# simple.net
KiCad netlist of a schematic drawn in EAGLE
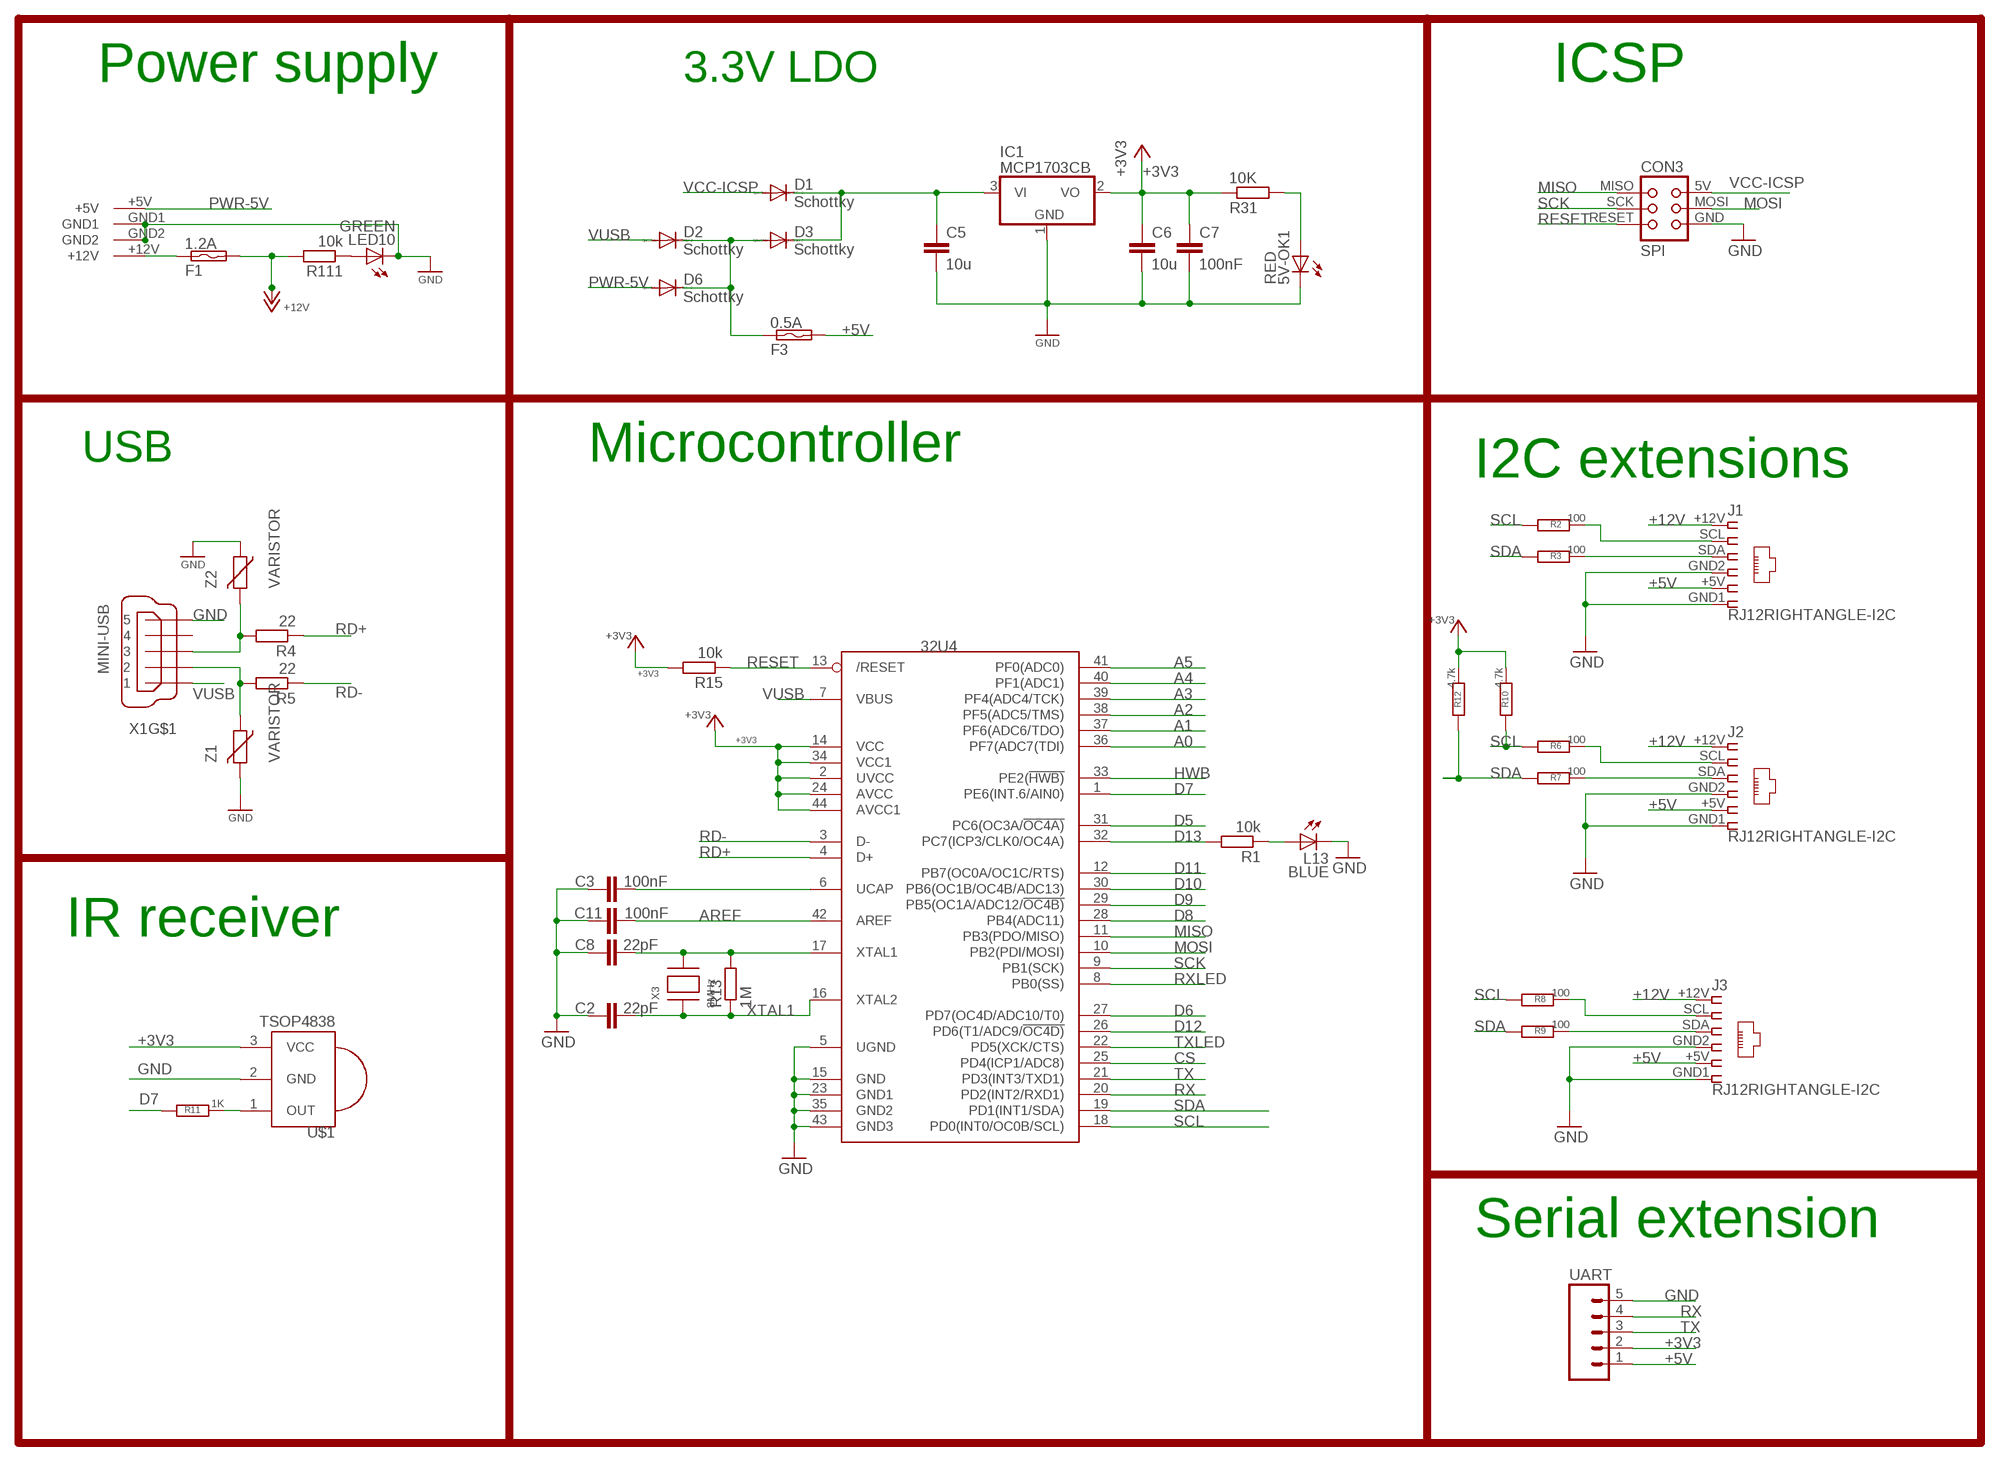
[diagram p0: schematic, sheet 1]

(export (version "E")
  (design (tool "Eeschema 10.0.6"))
  (components
    (comp (ref "5V-OK1")
      (value "RED")
      (footprint "eagle-import:CHIP-LED0805")
      (libsource (lib "eagle-import") (part "LEDCHIP-LED0805"))
    )
    (comp (ref "C2")
      (value "22pF")
      (footprint "eagle-import:C0805K")
      (libsource (lib "eagle-import") (part "C-EUC0805K"))
    )
    (comp (ref "C3")
      (value "100nF")
      (footprint "eagle-import:C0805K")
      (libsource (lib "eagle-import") (part "C-EUC0805K"))
    )
    (comp (ref "C5")
      (value "10u")
      (footprint "eagle-import:C0805K")
      (fields (field (name "MPN") "77-VJ1206V106ZXQTBC"))
      (libsource (lib "eagle-import") (part "rcl_334_C-EUC0805K"))
    )
    (comp (ref "C6")
      (value "10u")
      (footprint "eagle-import:C0805K")
      (fields (field (name "MPN") "77-VJ1206V106ZXQTBC"))
      (libsource (lib "eagle-import") (part "rcl_334_C-EUC0805K"))
    )
    (comp (ref "C7")
      (value "100nF")
      (footprint "eagle-import:C0805K")
      (fields (field (name "MPN") "80-C1206C104K5R"))
      (libsource (lib "eagle-import") (part "rcl_334_C-EUC0805K"))
    )
    (comp (ref "C8")
      (value "22pF")
      (footprint "eagle-import:C0805K")
      (libsource (lib "eagle-import") (part "C-EUC0805K"))
    )
    (comp (ref "C11")
      (value "100nF")
      (footprint "eagle-import:C0805K")
      (libsource (lib "eagle-import") (part "C-EUC0805K"))
    )
    (comp (ref "CON3")
      (value "SPI")
      (footprint "eagle-import:TC2030-MCP-NL")
      (libsource (lib "eagle-import") (part "TINYISPT"))
    )
    (comp (ref "D1")
      (value "Schottky")
      (footprint "eagle-import:SOD123")
      (fields (field (name "MPN") "621-1N5819HW-F"))
      (libsource (lib "eagle-import") (part "MBR0520LT"))
    )
    (comp (ref "D2")
      (value "Schottky")
      (footprint "eagle-import:SOD123")
      (fields (field (name "MPN") "621-1N5819HW-F"))
      (libsource (lib "eagle-import") (part "MBR0520LT"))
    )
    (comp (ref "D3")
      (value "Schottky")
      (footprint "eagle-import:SOD123")
      (fields (field (name "MPN") "621-1N5819HW-F"))
      (libsource (lib "eagle-import") (part "MBR0520LT"))
    )
    (comp (ref "D6")
      (value "Schottky")
      (footprint "eagle-import:SOD123")
      (fields (field (name "MPN") "621-1N5819HW-F"))
      (libsource (lib "eagle-import") (part "MBR0520LT"))
    )
    (comp (ref "F1")
      (value "1.2A")
      (footprint "eagle-import:C1812")
      (libsource (lib "eagle-import") (part "POLYSWITCHSMD1812"))
    )
    (comp (ref "F3")
      (value "0.5A")
      (footprint "eagle-import:C1812")
      (libsource (lib "eagle-import") (part "POLYSWITCHSMD1812"))
    )
    (comp (ref "IC1")
      (value "MCP1703CB")
      (footprint "eagle-import:SOT23")
      (libsource (lib "eagle-import") (part "MCP1703CB"))
    )
    (comp (ref "J1")
      (value "RJ12RIGHTANGLE-I2C")
      (footprint "eagle-import:RJ12-RIGHTANGLE-I2C")
      (libsource (lib "eagle-import") (part "RJ12RIGHTANGLE-I2C"))
    )
    (comp (ref "J2")
      (value "RJ12RIGHTANGLE-I2C")
      (footprint "eagle-import:RJ12-RIGHTANGLE-I2C")
      (libsource (lib "eagle-import") (part "RJ12RIGHTANGLE-I2C"))
    )
    (comp (ref "J3")
      (value "RJ12RIGHTANGLE-I2C")
      (footprint "eagle-import:RJ12-RIGHTANGLE-I2C")
      (libsource (lib "eagle-import") (part "RJ12RIGHTANGLE-I2C"))
    )
    (comp (ref "L13")
      (value "BLUE")
      (footprint "eagle-import:CHIP-LED0805")
      (libsource (lib "eagle-import") (part "LEDCHIP-LED0805"))
    )
    (comp (ref "LED10")
      (value "GREEN")
      (footprint "eagle-import:CHIP-LED0805")
      (libsource (lib "eagle-import") (part "LEDCHIP-LED0805"))
    )
    (comp (ref "R1")
      (value "10k")
      (footprint "eagle-import:M0805")
      (libsource (lib "eagle-import") (part "resistor_348_R-EU_M0805"))
    )
    (comp (ref "R2")
      (value "100")
      (footprint "eagle-import:R0805")
      (libsource (lib "eagle-import") (part "resistor_348_R-EU_R0805"))
    )
    (comp (ref "R3")
      (value "100")
      (footprint "eagle-import:R0805")
      (libsource (lib "eagle-import") (part "resistor_348_R-EU_R0805"))
    )
    (comp (ref "R4")
      (value "22")
      (footprint "eagle-import:R0805")
      (libsource (lib "eagle-import") (part "R-EU_R0805"))
    )
    (comp (ref "R5")
      (value "22")
      (footprint "eagle-import:R0805")
      (libsource (lib "eagle-import") (part "rcl_334_R-EU_R0805"))
    )
    (comp (ref "R6")
      (value "100")
      (footprint "eagle-import:R0805")
      (libsource (lib "eagle-import") (part "resistor_348_R-EU_R0805"))
    )
    (comp (ref "R7")
      (value "100")
      (footprint "eagle-import:R0805")
      (libsource (lib "eagle-import") (part "resistor_348_R-EU_R0805"))
    )
    (comp (ref "R8")
      (value "100")
      (footprint "eagle-import:R0805")
      (libsource (lib "eagle-import") (part "resistor_348_R-EU_R0805"))
    )
    (comp (ref "R9")
      (value "100")
      (footprint "eagle-import:R0805")
      (libsource (lib "eagle-import") (part "resistor_348_R-EU_R0805"))
    )
    (comp (ref "R10")
      (value "4.7k")
      (footprint "eagle-import:R0805")
      (libsource (lib "eagle-import") (part "resistor_348_R-EU_R0805"))
    )
    (comp (ref "R11")
      (value "1K")
      (footprint "eagle-import:R0805")
      (libsource (lib "eagle-import") (part "resistor_348_R-EU_R0805"))
    )
    (comp (ref "R12")
      (value "4.7k")
      (footprint "eagle-import:R0805")
      (libsource (lib "eagle-import") (part "resistor_348_R-EU_R0805"))
    )
    (comp (ref "R13")
      (value "1M")
      (footprint "eagle-import:M0805")
      (libsource (lib "eagle-import") (part "R-EU_M0805"))
    )
    (comp (ref "R15")
      (value "10k")
      (footprint "eagle-import:M0805")
      (libsource (lib "eagle-import") (part "resistor_348_R-EU_M0805"))
    )
    (comp (ref "R31")
      (value "10K")
      (footprint "eagle-import:R0805")
      (libsource (lib "eagle-import") (part "resistor_348_R-EU_R0805"))
    )
    (comp (ref "R111")
      (value "10k")
      (footprint "eagle-import:R0805")
      (libsource (lib "eagle-import") (part "R-EU_R0805"))
    )
    (comp (ref "U$1")
      (value "TSOP4838")
      (footprint "eagle-import:PNA460XM")
      (libsource (lib "eagle-import") (part "PNA460XM"))
    )
    (comp (ref "U$4")
      (value "32U4")
      (footprint "eagle-import:TQFP44")
      (libsource (lib "eagle-import") (part "ATMEGA32U4-AU"))
    )
    (comp (ref "U$6")
      (value "KPJX-4S-S")
      (footprint "eagle-import:KPJX-4S-S")
      (libsource (lib "eagle-import") (part "KPJX-4S-S"))
    )
    (comp (ref "UART")
      (value "M05PTH")
      (footprint "eagle-import:1X05")
      (libsource (lib "eagle-import") (part "M05PTH"))
    )
    (comp (ref "X1")
      (value "MINI-USB")
      (footprint "eagle-import:32005-201")
      (fields (field (name "MPN") "649-10033526-N3212LF"))
      (libsource (lib "eagle-import") (part "MINI-USB-SCHIELD-32005-201"))
    )
    (comp (ref "X3")
      (value "8MHz")
      (footprint "eagle-import:NX6035")
      (libsource (lib "eagle-import") (part "XTALNX6035"))
    )
    (comp (ref "Z1")
      (value "VARISTOR")
      (footprint "eagle-import:CT_CN0603")
      (libsource (lib "eagle-import") (part "VARISTORCN0603"))
    )
    (comp (ref "Z2")
      (value "VARISTOR")
      (footprint "eagle-import:CT_CN0603")
      (libsource (lib "eagle-import") (part "VARISTORCN0603"))
    )
  )
  (nets
    (net (code "1") (name "+3V3") (class "Default")
      (node (ref "C6") (pin "1") (pinfunction "1_1") (pintype "passive"))
      (node (ref "C7") (pin "1") (pinfunction "1_1") (pintype "passive"))
      (node (ref "IC1") (pin "2") (pinfunction "VO_2") (pintype "passive"))
      (node (ref "R10") (pin "1") (pinfunction "1_1") (pintype "passive"))
      (node (ref "R12") (pin "1") (pinfunction "1_1") (pintype "passive"))
      (node (ref "R15") (pin "2") (pinfunction "2_2") (pintype "passive"))
      (node (ref "R31") (pin "1") (pinfunction "1_1") (pintype "passive"))
      (node (ref "U$1") (pin "3") (pinfunction "VCC_3") (pintype "power_in"))
      (node (ref "U$4") (pin "14") (pinfunction "VCC_14") (pintype "bidirectional"))
      (node (ref "U$4") (pin "2") (pinfunction "UVCC_2") (pintype "bidirectional"))
      (node (ref "U$4") (pin "24") (pinfunction "AVCC_24") (pintype "bidirectional"))
      (node (ref "U$4") (pin "34") (pinfunction "VCC1_34") (pintype "bidirectional"))
      (node (ref "U$4") (pin "44") (pinfunction "AVCC1_44") (pintype "bidirectional"))
      (node (ref "UART") (pin "2") (pinfunction "2_2") (pintype "passive"))
    )
    (net (code "2") (name "+12V") (class "Default")
      (node (ref "F1") (pin "2") (pinfunction "2_2") (pintype "passive"))
      (node (ref "J1") (pin "+12V") (pinfunction "1_+12V") (pintype "bidirectional"))
      (node (ref "J2") (pin "+12V") (pinfunction "1_+12V") (pintype "bidirectional"))
      (node (ref "J3") (pin "+12V") (pinfunction "1_+12V") (pintype "bidirectional"))
      (node (ref "R111") (pin "2") (pinfunction "2_2") (pintype "passive"))
    )
    (net (code "3") (name "/+5V") (class "Default")
      (node (ref "F3") (pin "2") (pinfunction "2_2") (pintype "passive"))
      (node (ref "J1") (pin "+5V") (pinfunction "5_+5V") (pintype "bidirectional"))
      (node (ref "J2") (pin "+5V") (pinfunction "5_+5V") (pintype "bidirectional"))
      (node (ref "J3") (pin "+5V") (pinfunction "5_+5V") (pintype "bidirectional"))
      (node (ref "UART") (pin "1") (pinfunction "1_1") (pintype "passive"))
    )
    (net (code "4") (name "/A0") (class "Default")
      (node (ref "U$4") (pin "36") (pinfunction "PF7(ADC7(TDI)_36") (pintype "bidirectional"))
    )
    (net (code "5") (name "/A1") (class "Default")
      (node (ref "U$4") (pin "37") (pinfunction "PF6(ADC6/TDO)_37") (pintype "bidirectional"))
    )
    (net (code "6") (name "/A2") (class "Default")
      (node (ref "U$4") (pin "38") (pinfunction "PF5(ADC5/TMS)_38") (pintype "bidirectional"))
    )
    (net (code "7") (name "/A3") (class "Default")
      (node (ref "U$4") (pin "39") (pinfunction "PF4(ADC4/TCK)_39") (pintype "bidirectional"))
    )
    (net (code "8") (name "/A4") (class "Default")
      (node (ref "U$4") (pin "40") (pinfunction "PF1(ADC1)_40") (pintype "bidirectional"))
    )
    (net (code "9") (name "/A5") (class "Default")
      (node (ref "U$4") (pin "41") (pinfunction "PF0(ADC0)_41") (pintype "bidirectional"))
    )
    (net (code "10") (name "/AREF") (class "Default")
      (node (ref "C11") (pin "1") (pinfunction "1_1") (pintype "passive"))
      (node (ref "U$4") (pin "42") (pinfunction "AREF_42") (pintype "bidirectional"))
    )
    (net (code "11") (name "/CS") (class "Default")
      (node (ref "U$4") (pin "25") (pinfunction "PD4(ICP1/ADC8)_25") (pintype "bidirectional"))
    )
    (net (code "12") (name "/D5") (class "Default")
      (node (ref "U$4") (pin "31") (pinfunction "PC6(OC3A/~{OC4A})_31") (pintype "bidirectional"))
    )
    (net (code "13") (name "/D6") (class "Default")
      (node (ref "U$4") (pin "27") (pinfunction "PD7(OC4D/ADC10/T0)_27") (pintype "bidirectional"))
    )
    (net (code "14") (name "/D7") (class "Default")
      (node (ref "R11") (pin "2") (pinfunction "2_2") (pintype "passive"))
      (node (ref "U$4") (pin "1") (pinfunction "PE6(INT.6/AIN0)_1") (pintype "bidirectional"))
    )
    (net (code "15") (name "/D8") (class "Default")
      (node (ref "U$4") (pin "28") (pinfunction "PB4(ADC11)_28") (pintype "bidirectional"))
    )
    (net (code "16") (name "/D9") (class "Default")
      (node (ref "U$4") (pin "29") (pinfunction "PB5(OC1A/ADC12/~{OC4B})_29") (pintype "bidirectional"))
    )
    (net (code "17") (name "/D10") (class "Default")
      (node (ref "U$4") (pin "30") (pinfunction "PB6(OC1B/OC4B/ADC13)_30") (pintype "bidirectional"))
    )
    (net (code "18") (name "/D11") (class "Default")
      (node (ref "U$4") (pin "12") (pinfunction "PB7(OC0A/OC1C/RTS)_12") (pintype "bidirectional"))
    )
    (net (code "19") (name "/D12") (class "Default")
      (node (ref "U$4") (pin "26") (pinfunction "PD6(T1/ADC9/~{OC4D})_26") (pintype "bidirectional"))
    )
    (net (code "20") (name "/D13") (class "Default")
      (node (ref "R1") (pin "2") (pinfunction "2_2") (pintype "passive"))
      (node (ref "U$4") (pin "32") (pinfunction "PC7(ICP3/CLK0/OC4A)_32") (pintype "bidirectional"))
    )
    (net (code "21") (name "/HWB") (class "Default")
      (node (ref "U$4") (pin "33") (pinfunction "PE2(~{HWB})_33") (pintype "bidirectional"))
    )
    (net (code "22") (name "/MISO") (class "Default")
      (node (ref "CON3") (pin "MISO") (pinfunction "MISO_MISO") (pintype "passive"))
      (node (ref "U$4") (pin "11") (pinfunction "PB3(PDO/MISO)_11") (pintype "bidirectional"))
    )
    (net (code "23") (name "/MOSI") (class "Default")
      (node (ref "CON3") (pin "MOSI") (pinfunction "MOSI_MOSI") (pintype "passive"))
      (node (ref "U$4") (pin "10") (pinfunction "PB2(PDI/MOSI)_10") (pintype "bidirectional"))
    )
    (net (code "24") (name "/PWR-5V") (class "Default")
      (node (ref "D6") (pin "A") (pinfunction "A_A") (pintype "passive"))
      (node (ref "U$6") (pin "+5V") (pinfunction "+5V_+5V") (pintype "power_in"))
    )
    (net (code "25") (name "/RD+") (class "Default")
      (node (ref "R4") (pin "1") (pinfunction "1_1") (pintype "passive"))
      (node (ref "U$4") (pin "4") (pinfunction "D+_4") (pintype "bidirectional"))
    )
    (net (code "26") (name "/RD-") (class "Default")
      (node (ref "R5") (pin "1") (pinfunction "1_1") (pintype "passive"))
      (node (ref "U$4") (pin "3") (pinfunction "D-_3") (pintype "bidirectional"))
    )
    (net (code "27") (name "/RESET") (class "Default")
      (node (ref "CON3") (pin "RESET") (pinfunction "RESET_RESET") (pintype "passive"))
      (node (ref "R15") (pin "1") (pinfunction "1_1") (pintype "passive"))
      (node (ref "U$4") (pin "13") (pinfunction "/RESET_13") (pintype "bidirectional"))
    )
    (net (code "28") (name "/RX") (class "Default")
      (node (ref "U$4") (pin "20") (pinfunction "PD2(INT2/RXD1)_20") (pintype "bidirectional"))
      (node (ref "UART") (pin "4") (pinfunction "4_4") (pintype "passive"))
    )
    (net (code "29") (name "/RXLED") (class "Default")
      (node (ref "U$4") (pin "8") (pinfunction "PB0(SS)_8") (pintype "bidirectional"))
    )
    (net (code "30") (name "/SCK") (class "Default")
      (node (ref "CON3") (pin "SCK") (pinfunction "SCK_SCK") (pintype "passive"))
      (node (ref "U$4") (pin "9") (pinfunction "PB1(SCK)_9") (pintype "bidirectional"))
    )
    (net (code "31") (name "/SCL") (class "Default")
      (node (ref "R10") (pin "2") (pinfunction "2_2") (pintype "passive"))
      (node (ref "R2") (pin "2") (pinfunction "2_2") (pintype "passive"))
      (node (ref "R6") (pin "2") (pinfunction "2_2") (pintype "passive"))
      (node (ref "R8") (pin "2") (pinfunction "2_2") (pintype "passive"))
      (node (ref "U$4") (pin "18") (pinfunction "PD0(INT0/OC0B/SCL)_18") (pintype "bidirectional"))
    )
    (net (code "32") (name "/SDA") (class "Default")
      (node (ref "R12") (pin "2") (pinfunction "2_2") (pintype "passive"))
      (node (ref "R3") (pin "2") (pinfunction "2_2") (pintype "passive"))
      (node (ref "R7") (pin "2") (pinfunction "2_2") (pintype "passive"))
      (node (ref "R9") (pin "2") (pinfunction "2_2") (pintype "passive"))
      (node (ref "U$4") (pin "19") (pinfunction "PD1(INT1/SDA)_19") (pintype "bidirectional"))
    )
    (net (code "33") (name "/TX") (class "Default")
      (node (ref "U$4") (pin "21") (pinfunction "PD3(INT3/TXD1)_21") (pintype "bidirectional"))
      (node (ref "UART") (pin "3") (pinfunction "3_3") (pintype "passive"))
    )
    (net (code "34") (name "/TXLED") (class "Default")
      (node (ref "U$4") (pin "22") (pinfunction "PD5(XCK/CTS)_22") (pintype "bidirectional"))
    )
    (net (code "35") (name "/VCC-ICSP") (class "Default")
      (node (ref "CON3") (pin "5V") (pinfunction "VCC_5V") (pintype "passive"))
      (node (ref "D1") (pin "A") (pinfunction "A_A") (pintype "passive"))
    )
    (net (code "36") (name "/VUSB") (class "Default")
      (node (ref "D2") (pin "A") (pinfunction "A_A") (pintype "passive"))
      (node (ref "U$4") (pin "7") (pinfunction "VBUS_7") (pintype "bidirectional"))
      (node (ref "X1") (pin "1") (pinfunction "1_1") (pintype "passive"))
    )
    (net (code "37") (name "/XTAL1") (class "Default")
      (node (ref "C2") (pin "2") (pinfunction "2_2") (pintype "passive"))
      (node (ref "R13") (pin "1") (pinfunction "1_1") (pintype "passive"))
      (node (ref "U$4") (pin "16") (pinfunction "XTAL2_16") (pintype "bidirectional"))
      (node (ref "X3") (pin "P$1") (pinfunction "P$1_P$1") (pintype "bidirectional"))
    )
    (net (code "38") (name "GND") (class "Default")
      (node (ref "5V-OK1") (pin "C") (pinfunction "C_C") (pintype "passive"))
      (node (ref "C11") (pin "2") (pinfunction "2_2") (pintype "passive"))
      (node (ref "C2") (pin "1") (pinfunction "1_1") (pintype "passive"))
      (node (ref "C3") (pin "1") (pinfunction "1_1") (pintype "passive"))
      (node (ref "C5") (pin "2") (pinfunction "2_2") (pintype "passive"))
      (node (ref "C6") (pin "2") (pinfunction "2_2") (pintype "passive"))
      (node (ref "C7") (pin "2") (pinfunction "2_2") (pintype "passive"))
      (node (ref "C8") (pin "1") (pinfunction "1_1") (pintype "passive"))
      (node (ref "CON3") (pin "GND") (pinfunction "GND_GND") (pintype "passive"))
      (node (ref "IC1") (pin "1") (pinfunction "GND_1") (pintype "passive"))
      (node (ref "J1") (pin "GND1") (pinfunction "6_GND1") (pintype "bidirectional"))
      (node (ref "J1") (pin "GND2") (pinfunction "4_GND2") (pintype "bidirectional"))
      (node (ref "J2") (pin "GND1") (pinfunction "6_GND1") (pintype "bidirectional"))
      (node (ref "J2") (pin "GND2") (pinfunction "4_GND2") (pintype "bidirectional"))
      (node (ref "J3") (pin "GND1") (pinfunction "6_GND1") (pintype "bidirectional"))
      (node (ref "J3") (pin "GND2") (pinfunction "4_GND2") (pintype "bidirectional"))
      (node (ref "L13") (pin "C") (pinfunction "C_C") (pintype "passive"))
      (node (ref "LED10") (pin "C") (pinfunction "C_C") (pintype "passive"))
      (node (ref "U$1") (pin "2") (pinfunction "GND_2") (pintype "power_in"))
      (node (ref "U$4") (pin "15") (pinfunction "GND_15") (pintype "bidirectional"))
      (node (ref "U$4") (pin "23") (pinfunction "GND1_23") (pintype "bidirectional"))
      (node (ref "U$4") (pin "35") (pinfunction "GND2_35") (pintype "bidirectional"))
      (node (ref "U$4") (pin "43") (pinfunction "GND3_43") (pintype "bidirectional"))
      (node (ref "U$4") (pin "5") (pinfunction "UGND_5") (pintype "bidirectional"))
      (node (ref "U$6") (pin "GND1") (pinfunction "GND1_GND1") (pintype "input"))
      (node (ref "U$6") (pin "GND2") (pinfunction "GND2_GND2") (pintype "input"))
      (node (ref "UART") (pin "5") (pinfunction "5_5") (pintype "passive"))
      (node (ref "X1") (pin "5") (pinfunction "5_5") (pintype "passive"))
      (node (ref "Z1") (pin "2") (pinfunction "2_2") (pintype "passive"))
      (node (ref "Z2") (pin "1") (pinfunction "1_1") (pintype "passive"))
    )
    (net (code "39") (name "Net-(5V-OK1-PadA)") (class "Default")
      (node (ref "5V-OK1") (pin "A") (pinfunction "A_A") (pintype "passive"))
      (node (ref "R31") (pin "2") (pinfunction "2_2") (pintype "passive"))
    )
    (net (code "40") (name "Net-(D2-PadC)") (class "Default")
      (node (ref "D2") (pin "C") (pinfunction "C_C") (pintype "passive"))
      (node (ref "D3") (pin "A") (pinfunction "A_A") (pintype "passive"))
      (node (ref "D6") (pin "C") (pinfunction "C_C") (pintype "passive"))
      (node (ref "F3") (pin "1") (pinfunction "1_1") (pintype "passive"))
    )
    (net (code "41") (name "Net-(F1-Pad1)") (class "Default")
      (node (ref "F1") (pin "1") (pinfunction "1_1") (pintype "passive"))
      (node (ref "U$6") (pin "+12V") (pinfunction "+12V_+12V") (pintype "power_in"))
    )
    (net (code "42") (name "Net-(IC1-VI)") (class "Default")
      (node (ref "C5") (pin "1") (pinfunction "1_1") (pintype "passive"))
      (node (ref "D1") (pin "C") (pinfunction "C_C") (pintype "passive"))
      (node (ref "D3") (pin "C") (pinfunction "C_C") (pintype "passive"))
      (node (ref "IC1") (pin "3") (pinfunction "VI_3") (pintype "input"))
    )
    (net (code "43") (name "Net-(J1-2)") (class "Default")
      (node (ref "J1") (pin "SCL") (pinfunction "2_SCL") (pintype "bidirectional"))
      (node (ref "R2") (pin "1") (pinfunction "1_1") (pintype "passive"))
    )
    (net (code "44") (name "Net-(J1-3)") (class "Default")
      (node (ref "J1") (pin "SDA") (pinfunction "3_SDA") (pintype "bidirectional"))
      (node (ref "R3") (pin "1") (pinfunction "1_1") (pintype "passive"))
    )
    (net (code "45") (name "Net-(J2-2)") (class "Default")
      (node (ref "J2") (pin "SCL") (pinfunction "2_SCL") (pintype "bidirectional"))
      (node (ref "R6") (pin "1") (pinfunction "1_1") (pintype "passive"))
    )
    (net (code "46") (name "Net-(J2-3)") (class "Default")
      (node (ref "J2") (pin "SDA") (pinfunction "3_SDA") (pintype "bidirectional"))
      (node (ref "R7") (pin "1") (pinfunction "1_1") (pintype "passive"))
    )
    (net (code "47") (name "Net-(J3-2)") (class "Default")
      (node (ref "J3") (pin "SCL") (pinfunction "2_SCL") (pintype "bidirectional"))
      (node (ref "R8") (pin "1") (pinfunction "1_1") (pintype "passive"))
    )
    (net (code "48") (name "Net-(J3-3)") (class "Default")
      (node (ref "J3") (pin "SDA") (pinfunction "3_SDA") (pintype "bidirectional"))
      (node (ref "R9") (pin "1") (pinfunction "1_1") (pintype "passive"))
    )
    (net (code "49") (name "Net-(L13-PadA)") (class "Default")
      (node (ref "L13") (pin "A") (pinfunction "A_A") (pintype "passive"))
      (node (ref "R1") (pin "1") (pinfunction "1_1") (pintype "passive"))
    )
    (net (code "50") (name "Net-(LED10-PadA)") (class "Default")
      (node (ref "LED10") (pin "A") (pinfunction "A_A") (pintype "passive"))
      (node (ref "R111") (pin "1") (pinfunction "1_1") (pintype "passive"))
    )
    (net (code "51") (name "Net-(R4-Pad2)") (class "Default")
      (node (ref "R4") (pin "2") (pinfunction "2_2") (pintype "passive"))
      (node (ref "X1") (pin "3") (pinfunction "3_3") (pintype "passive"))
      (node (ref "Z2") (pin "2") (pinfunction "2_2") (pintype "passive"))
    )
    (net (code "52") (name "Net-(R5-Pad2)") (class "Default")
      (node (ref "R5") (pin "2") (pinfunction "2_2") (pintype "passive"))
      (node (ref "X1") (pin "2") (pinfunction "2_2") (pintype "passive"))
      (node (ref "Z1") (pin "1") (pinfunction "1_1") (pintype "passive"))
    )
    (net (code "53") (name "Net-(U$1-OUT)") (class "Default")
      (node (ref "R11") (pin "1") (pinfunction "1_1") (pintype "passive"))
      (node (ref "U$1") (pin "1") (pinfunction "OUT_1") (pintype "output"))
    )
    (net (code "54") (name "Net-(U$4-UCAP)") (class "Default")
      (node (ref "C3") (pin "2") (pinfunction "2_2") (pintype "passive"))
      (node (ref "U$4") (pin "6") (pinfunction "UCAP_6") (pintype "bidirectional"))
    )
    (net (code "55") (name "Net-(U$4-XTAL1)") (class "Default")
      (node (ref "C8") (pin "2") (pinfunction "2_2") (pintype "passive"))
      (node (ref "R13") (pin "2") (pinfunction "2_2") (pintype "passive"))
      (node (ref "U$4") (pin "17") (pinfunction "XTAL1_17") (pintype "bidirectional"))
      (node (ref "X3") (pin "P$2") (pinfunction "P$2_P$2") (pintype "bidirectional"))
    )
    (net (code "56") (name "unconnected-(X1-Pad4)") (class "Default")
      (node (ref "X1") (pin "4") (pinfunction "4_4") (pintype "passive"))
    )
  )
)
